# AICat.net
KiCad netlist of a schematic drawn in Altium Designer
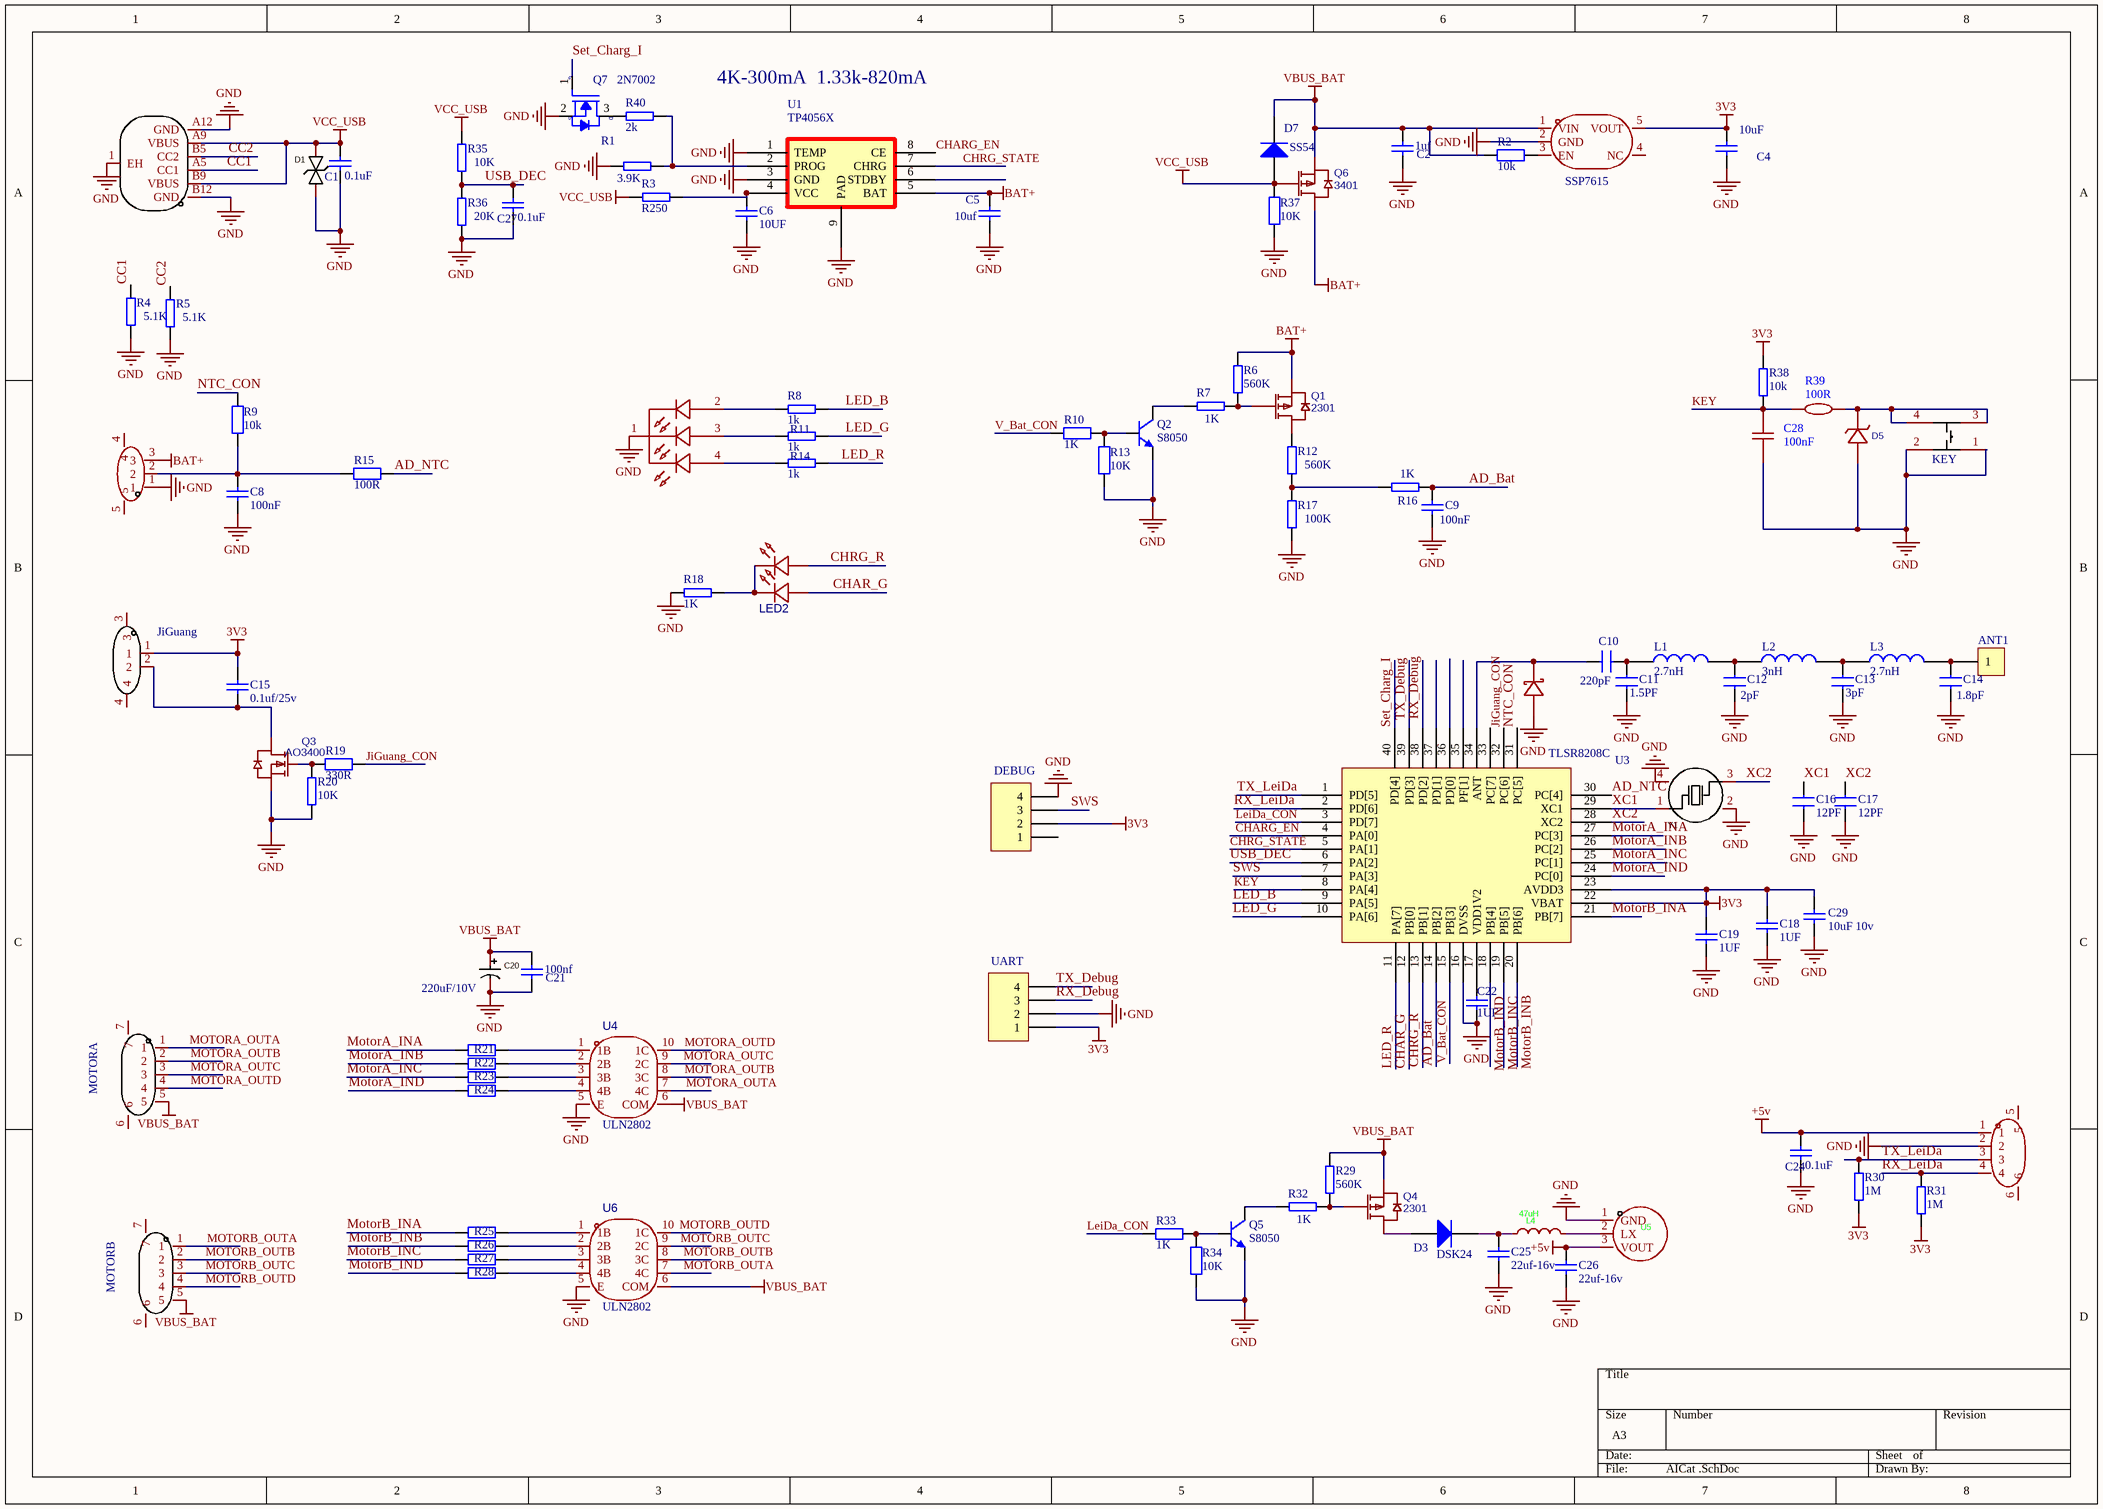
[diagram p0: AICat .SchDoc]

(export (version "E")
  (design (tool "Eeschema 10.0.6"))
  (components
    (comp (ref "ANT1")
      (value "~")
      (footprint "tp")
      (description "Connector")
      (libsource (lib "*") (part "CON1"))
    )
    (comp (ref "BAT1")
      (value "BX-PH2.0-3PWT")
      (footprint "HDR-TH_3P-P2.50_ZX-XH2.54-3PWZ")
      (libsource (lib "altium-import") (part "root_2_BX-PH2.0-3PWT_"))
    )
    (comp (ref "C1")
      (value "0.1uF")
      (footprint "0603_C")
      (description "Capacitor")
      (fields (field (name "PUBLISHER") "Altium Limited"))
      (libsource (lib "*") (part "Cap"))
    )
    (comp (ref "C2")
      (value "1uf")
      (footprint "0603_C")
      (description "无极电容")
      (libsource (lib "电容电阻电感保险") (part "Cap1"))
    )
    (comp (ref "C4")
      (value "10uF")
      (footprint "0603_C")
      (description "Capacitor")
      (fields (field (name "PUBLISHER") "Altium Limited"))
      (libsource (lib "*") (part "Cap"))
    )
    (comp (ref "C5")
      (value "10uf")
      (footprint "0603_C")
      (description "Capacitor")
      (fields (field (name "PUBLISHER") "Altium Limited"))
      (libsource (lib "*") (part "Cap"))
    )
    (comp (ref "C6") (value "10UF") (footprint "0603_c") (libsource (lib "DIY") (part "CAP")))
    (comp (ref "C8") (value "100nF") (footprint "0603_C") (libsource (lib "DIY") (part "CAP")))
    (comp (ref "C9") (value "100nF") (footprint "0603_C") (libsource (lib "DIY") (part "CAP")))
    (comp (ref "C10")
      (value "220pF")
      (footprint "C0402")
      (description "Capacitor")
      (libsource (lib "*") (part "CAP"))
    )
    (comp (ref "C11")
      (value "1.5PF")
      (footprint "C0402")
      (description "Capacitor")
      (libsource (lib "*") (part "CAP"))
    )
    (comp (ref "C12")
      (value "2pF")
      (footprint "C0402")
      (description "Capacitor")
      (libsource (lib "*") (part "CAP"))
    )
    (comp (ref "C13")
      (value "3pF")
      (footprint "C0402")
      (description "Capacitor")
      (libsource (lib "*") (part "CAP"))
    )
    (comp (ref "C14")
      (value "1.8pF")
      (footprint "C0402")
      (description "Capacitor")
      (libsource (lib "*") (part "CAP"))
    )
    (comp (ref "C15")
      (value "0.1uf/25v")
      (footprint "0603_C")
      (description "Capacitor")
      (fields (field (name "PUBLISHER") "Altium Limited"))
      (libsource (lib "*") (part "Cap"))
    )
    (comp (ref "C16")
      (value "12PF")
      (footprint "0603_c")
      (description "Capacitor")
      (libsource (lib "*") (part "CAP"))
    )
    (comp (ref "C17")
      (value "12PF")
      (footprint "0603_c")
      (description "Capacitor")
      (libsource (lib "*") (part "CAP"))
    )
    (comp (ref "C18") (value "1UF") (footprint "0603_c") (libsource (lib "DIY") (part "CAP")))
    (comp (ref "C19") (value "1UF") (footprint "0603_c") (libsource (lib "DIY") (part "CAP")))
    (comp (ref "C20")
      (value "220uF/10V")
      (footprint "SMD 6.3*5.4 电解")
      (fields (field (name "MANUFACTURER PART") "RVT1A221M0605"))
      (libsource (lib "altium-import") (part "root_0_RVT1A221M0605_C72494_"))
    )
    (comp (ref "C21")
      (value "100nf")
      (footprint "0603_C")
      (description "无极电容")
      (libsource (lib "电容电阻电感保险") (part "Cap1"))
    )
    (comp (ref "C22") (value "1UF") (footprint "0603_c") (libsource (lib "DIY") (part "CAP")))
    (comp (ref "C24")
      (value "0.1uF")
      (footprint "0603_C")
      (description "Capacitor")
      (fields (field (name "PUBLISHER") "Altium Limited"))
      (libsource (lib "*") (part "Cap"))
    )
    (comp (ref "C25")
      (value "22uf-16v")
      (footprint "0805_c")
      (description "无极电容")
      (libsource (lib "电容电阻电感保险") (part "Cap1"))
    )
    (comp (ref "C26")
      (value "22uf-16v")
      (footprint "0805_c")
      (description "无极电容")
      (libsource (lib "电容电阻电感保险") (part "Cap1"))
    )
    (comp (ref "C27")
      (value "0.1uF")
      (footprint "0603_C")
      (description "Capacitor")
      (fields (field (name "PUBLISHER") "Altium Limited"))
      (libsource (lib "*") (part "Cap"))
    )
    (comp (ref "C28")
      (value "100nF")
      (footprint "0603_c")
      (libsource (lib "altium-import") (part "root_1_CAP_0603_"))
    )
    (comp (ref "C29")
      (value "10uF 10v")
      (footprint "0603_C")
      (description "Capacitor")
      (fields (field (name "PUBLISHER") "Altium Limited"))
      (libsource (lib "*") (part "Cap"))
    )
    (comp (ref "CN1")
      (value "JiGuang")
      (footprint "CONN-SMD_2P-P1.25-LT")
      (fields (field (name "MANUFACTURER PART") "HC-1.25-2PLT"))
      (libsource (lib "altium-import") (part "root_0_mirrored_HC-1.25-2PLT_"))
    )
    (comp (ref "CN2")
      (value "HC-1.25-4PLT")
      (footprint "CONN-SMD_4P-P1.25_LT")
      (libsource (lib "altium-import") (part "root_0_HC-1.25-4PLT_"))
    )
    (comp (ref "D1")
      (value "SMF5.0CA_C726939")
      (footprint "SOD-123 双向")
      (fields (field (name "MANUFACTURER PART") "SMF5.0CA"))
      (libsource (lib "altium-import") (part "root_1_SMF5.0CA_C726939_"))
    )
    (comp (ref "D2")
      (value "SE6V3LHN102T 6.3v单向")
      (footprint "0402-D")
      (libsource (lib "altium-import") (part "root_3_TPNSR05F20NXT5G_"))
    )
    (comp (ref "D3")
      (value "DSK24")
      (footprint "SOD-123FL")
      (description "High Conductance Fast Diode")
      (fields (field (name "PUBLISHER") "Altium Limited"))
      (libsource (lib "Miscellaneous Devices") (part "Diode 1N4148"))
    )
    (comp (ref "D5")
      (value "esd5z5.0t1g-ms")
      (footprint "SOD-523_L1.2-W0.8-LS1.6-RD")
      (fields (field (name "MANUFACTURERPART") "ESD5Z5.0T1G-MS"))
      (libsource (lib "altium-import") (part "root_3_esd5z5.0t1g-ms_"))
    )
    (comp (ref "D7")
      (value "SS54")
      (footprint "SMA")
      (description "High Conductance Fast Diode")
      (fields (field (name "PUBLISHER") "Altium Limited"))
      (libsource (lib "Miscellaneous Devices") (part "Diode 1N4148"))
    )
    (comp (ref "J1")
      (value "MOTORA")
      (footprint "CONN-SMD_1.25-5PLT")
      (fields (field (name "MANUFACTURER PART") "HC-1.25-5PLT"))
      (libsource (lib "altium-import") (part "root_0_mirrored_HC-1.25-5PLT_"))
    )
    (comp (ref "J2")
      (value "MOTORB")
      (footprint "CONN-SMD_1.25-5PLT")
      (fields (field (name "MANUFACTURER PART") "HC-1.25-5PLT"))
      (libsource (lib "altium-import") (part "root_0_mirrored_HC-1.25-5PLT_"))
    )
    (comp (ref "K1")
      (value "KEY")
      (footprint "KEY_SMD_4P")
      (fields (field (name "MANUFACTURER PART") "TS-1002S-05026C"))
      (libsource (lib "altium-import") (part "root_2_TS-1002S-05026C_"))
    )
    (comp (ref "L1") (value "2.7nH") (footprint "R0402") (libsource (lib "*") (part "INDUCTOR")))
    (comp (ref "L2") (value "3nH") (footprint "R0402") (libsource (lib "*") (part "INDUCTOR")))
    (comp (ref "L3") (value "2.7nH") (footprint "R0402") (libsource (lib "*") (part "INDUCTOR")))
    (comp (ref "L4")
      (value "47uH")
      (footprint "IND-SMD_L3.5-W3.0_CD31")
      (fields (field (name "MANUFACTURER PART") "CD31-470M 47UH"))
      (libsource (lib "altium-import") (part "root_0_CD31-470M 47UH_"))
    )
    (comp (ref "LED1")
      (value "XL-A3528RGBC-BM")
      (footprint "LED-ARRAY-SMD_4P-L3.2-W2.8-LS3.5-BL_XL-A3528RGBC-BM")
      (libsource (lib "altium-import") (part "root_2_XL-A3528RGBC-BM_"))
    )
    (comp (ref "LED2")
      (value "*")
      (footprint "LED-SMD_4P-L3.2-W1.6-TL_XL-3216SURUGC")
      (libsource (lib "altium-import") (part "root_0_TJ-S2012SW8TCGLC2R2G-A5_"))
    )
    (comp (ref "P1")
      (value "DEBUG")
      (footprint "SIP4-2.54")
      (description "Header, 4-Pin")
      (fields (field (name "PUBLISHER") "Altium Limited"))
      (libsource (lib "Miscellaneous Connectors") (part "Header 4"))
    )
    (comp (ref "P2")
      (value "UART")
      (footprint "SIP4-2.54")
      (description "Header, 4-Pin")
      (fields (field (name "PUBLISHER") "Altium Limited"))
      (libsource (lib "Miscellaneous Connectors") (part "Header 4"))
    )
    (comp (ref "Q1")
      (value "2301")
      (footprint "SOT-23")
      (fields (field (name "BOM_MANUFACTURER PART") "CJ3401") (field (name "BOM_SUPPLIER PART") "C13799"))
      (libsource (lib "altium-import") (part "root_2_mirrored_CJ3401_"))
    )
    (comp (ref "Q2")
      (value "S8050")
      (footprint "SOT-23(SOT-23-3)")
      (description "NPN三极管")
      (libsource (lib "二三极管mos可控硅") (part "NPN_sot23"))
    )
    (comp (ref "Q3")
      (value "AO3400")
      (footprint "SOT-23")
      (fields
        (field (name "BOM_SUPPLIER PART") "C2890442")
        (field (name "BOM_MANUFACTURER PART") "JMTL3400A")
        (field (name "CONTRIBUTOR") "LCSC")
      )
      (libsource (lib "altium-import") (part "root_0_mirrored_JMTL3400A_"))
    )
    (comp (ref "Q4")
      (value "2301")
      (footprint "SOT-23")
      (fields (field (name "BOM_MANUFACTURER PART") "CJ3401") (field (name "BOM_SUPPLIER PART") "C13799"))
      (libsource (lib "altium-import") (part "root_2_mirrored_CJ3401_"))
    )
    (comp (ref "Q5")
      (value "S8050")
      (footprint "SOT-23(SOT-23-3)")
      (description "NPN三极管")
      (libsource (lib "二三极管mos可控硅") (part "NPN_sot23"))
    )
    (comp (ref "Q6")
      (value "3401")
      (footprint "SOT-23")
      (fields (field (name "BOM_MANUFACTURER PART") "CJ3401") (field (name "BOM_SUPPLIER PART") "C13799"))
      (libsource (lib "altium-import") (part "root_2_mirrored_CJ3401_"))
    )
    (comp (ref "Q7") (value "2N7002") (footprint "SOT-23") (libsource (lib "*") (part "AO3400_SOT23")))
    (comp (ref "R1") (value "3.9K") (footprint "0603_R") (libsource (lib "DIY") (part "RES")))
    (comp (ref "R2")
      (value "10k")
      (footprint "0603_R")
      (description "Resistor")
      (fields (field (name "PUBLISHER") "Altium Limited"))
      (libsource (lib "") (part "Res2_2"))
    )
    (comp (ref "R3") (value "R250") (footprint "1206_R") (libsource (lib "DIY") (part "RES")))
    (comp (ref "R4") (value "5.1K") (footprint "0603_R") (libsource (lib "DIY") (part "RES")))
    (comp (ref "R5") (value "5.1K") (footprint "0603_R") (libsource (lib "DIY") (part "RES")))
    (comp (ref "R6") (value "560K") (footprint "0603_R") (libsource (lib "*") (part "RES")))
    (comp (ref "R7") (value "1K") (footprint "0603_R") (libsource (lib "") (part "RES_1")))
    (comp (ref "R8") (value "1k") (footprint "0603_R") (libsource (lib "DIY") (part "RES")))
    (comp (ref "R9")
      (value "10k")
      (footprint "0603_R")
      (description "Resistor")
      (fields (field (name "PUBLISHER") "Altium Limited"))
      (libsource (lib "*") (part "Res2"))
    )
    (comp (ref "R10")
      (value "1K")
      (footprint "0603_r")
      (description "Resistor")
      (fields (field (name "PUBLISHER") "Altium Limited"))
      (libsource (lib "") (part "Res2_3"))
    )
    (comp (ref "R11") (value "1k") (footprint "0603_R") (libsource (lib "DIY") (part "RES")))
    (comp (ref "R12") (value "560K") (footprint "0603_R") (libsource (lib "DIY") (part "RES")))
    (comp (ref "R13")
      (value "10K")
      (footprint "0603_r")
      (description "Resistor")
      (fields (field (name "PUBLISHER") "Altium Limited"))
      (libsource (lib "") (part "Res2_2"))
    )
    (comp (ref "R14") (value "1k") (footprint "0603_R") (libsource (lib "DIY") (part "RES")))
    (comp (ref "R15")
      (value "100R")
      (footprint "0603_R")
      (description "Resistor")
      (fields (field (name "PUBLISHER") "Altium Limited"))
      (libsource (lib "") (part "Res2_4"))
    )
    (comp (ref "R16") (value "1K") (footprint "0603_R") (libsource (lib "DIY") (part "RES")))
    (comp (ref "R17") (value "100K") (footprint "0603_R") (libsource (lib "DIY") (part "RES")))
    (comp (ref "R18") (value "1K") (footprint "0603_R") (libsource (lib "DIY") (part "RES")))
    (comp (ref "R19")
      (value "330R")
      (footprint "0603_R")
      (description "Resistor")
      (fields (field (name "PUBLISHER") "Altium Limited"))
      (libsource (lib "*") (part "Res2"))
    )
    (comp (ref "R20") (value "10K") (footprint "0603_R") (libsource (lib "DIY") (part "RES")))
    (comp (ref "R21")
      (value "330R")
      (footprint "0603_R")
      (description "Resistor")
      (fields (field (name "PUBLISHER") "Altium Limited"))
      (libsource (lib "") (part "Res2_1"))
    )
    (comp (ref "R22")
      (value "330R")
      (footprint "0603_R")
      (description "Resistor")
      (fields (field (name "PUBLISHER") "Altium Limited"))
      (libsource (lib "") (part "Res2_1"))
    )
    (comp (ref "R23")
      (value "330R")
      (footprint "0603_R")
      (description "Resistor")
      (fields (field (name "PUBLISHER") "Altium Limited"))
      (libsource (lib "") (part "Res2_1"))
    )
    (comp (ref "R24")
      (value "330R")
      (footprint "0603_R")
      (description "Resistor")
      (fields (field (name "PUBLISHER") "Altium Limited"))
      (libsource (lib "") (part "Res2_1"))
    )
    (comp (ref "R25")
      (value "330R")
      (footprint "0603_R")
      (description "Resistor")
      (fields (field (name "PUBLISHER") "Altium Limited"))
      (libsource (lib "") (part "Res2_1"))
    )
    (comp (ref "R26")
      (value "330R")
      (footprint "0603_R")
      (description "Resistor")
      (fields (field (name "PUBLISHER") "Altium Limited"))
      (libsource (lib "") (part "Res2_1"))
    )
    (comp (ref "R27")
      (value "330R")
      (footprint "0603_R")
      (description "Resistor")
      (fields (field (name "PUBLISHER") "Altium Limited"))
      (libsource (lib "") (part "Res2_1"))
    )
    (comp (ref "R28")
      (value "330R")
      (footprint "0603_R")
      (description "Resistor")
      (fields (field (name "PUBLISHER") "Altium Limited"))
      (libsource (lib "") (part "Res2_1"))
    )
    (comp (ref "R29") (value "560K") (footprint "0603_R") (libsource (lib "*") (part "RES")))
    (comp (ref "R30") (value "1M") (footprint "0603_R") (libsource (lib "*") (part "RES")))
    (comp (ref "R31") (value "1M") (footprint "0603_R") (libsource (lib "*") (part "RES")))
    (comp (ref "R32") (value "1K") (footprint "0603_R") (libsource (lib "") (part "RES_1")))
    (comp (ref "R33")
      (value "1K")
      (footprint "0603_r")
      (description "Resistor")
      (fields (field (name "PUBLISHER") "Altium Limited"))
      (libsource (lib "") (part "Res2_3"))
    )
    (comp (ref "R34")
      (value "10K")
      (footprint "0603_r")
      (description "Resistor")
      (fields (field (name "PUBLISHER") "Altium Limited"))
      (libsource (lib "") (part "Res2_2"))
    )
    (comp (ref "R35") (value "10K") (footprint "0603_R") (libsource (lib "DIY") (part "RES")))
    (comp (ref "R36") (value "20K") (footprint "0603_R") (libsource (lib "DIY") (part "RES")))
    (comp (ref "R37")
      (value "10K")
      (footprint "0603_R")
      (description "Resistor")
      (fields (field (name "PUBLISHER") "Altium Limited"))
      (libsource (lib "*") (part "Res2"))
    )
    (comp (ref "R38") (value "10k") (footprint "0603_R") (libsource (lib "DIY") (part "RES")))
    (comp (ref "R39")
      (value "100R")
      (footprint "0603_r")
      (libsource (lib "altium-import") (part "root_2_Res_0603_"))
    )
    (comp (ref "R40") (value "2k") (footprint "0603_R") (libsource (lib "DIY") (part "RES")))
    (comp (ref "U1")
      (value "TP4056X")
      (footprint "SOP8-9")
      (description "TP4056")
      (libsource (lib "芯片") (part "TP4056"))
    )
    (comp (ref "U2")
      (value "SSP7615")
      (footprint "SOT-23-5")
      (libsource (lib "altium-import") (part "root_0_SSP7615-33M5R_"))
    )
    (comp (ref "U3")
      (value "TLSR8208C")
      (footprint "QFN-40_L5.0-W5.0-P0.40-BL-EP3.7")
      (libsource (lib "MyLib") (part "TLSR8208C"))
    )
    (comp (ref "U4")
      (value "ULN2802")
      (footprint "ESSOP-10")
      (libsource (lib "altium-import") (part "root_0_ULN2802_C2828555_"))
    )
    (comp (ref "U5")
      (value "HE9116A50NR")
      (footprint "SOT-23")
      (libsource (lib "altium-import") (part "root_0_HE9116A50NR_"))
    )
    (comp (ref "U6")
      (value "ULN2802")
      (footprint "ESSOP-10")
      (libsource (lib "altium-import") (part "root_0_ULN2802_C2828555_"))
    )
    (comp (ref "USB1")
      (value "TYPE-C 6P")
      (footprint "TPYE-C-6")
      (fields (field (name "MANUFACTURER PART") "TYPE-C 6P LTH6.5"))
      (libsource (lib "altium-import") (part "root_2_TYPE-C 6P LTH6.5_"))
    )
    (comp (ref "Y1")
      (value "24MHz +-20PPM")
      (footprint "CRYSTAL-SMD_4P-L3.2-W2.5")
      (fields (field (name "MANUFACTURER PART") "TAXM13.56M4RLBCCT2T"))
      (libsource (lib "altium-import") (part "root_0_TAXM13.56M4RLBCCT2T_"))
    )
  )
  (nets
    (net (code "1") (name "+5v") (class "Default")
      (node (ref "C24") (pin "2") (pinfunction "2_2") (pintype "passive"))
      (node (ref "C26") (pin "1") (pinfunction "1_1") (pintype "passive"))
      (node (ref "CN2") (pin "1") (pinfunction "1_1") (pintype "passive"))
      (node (ref "U5") (pin "3") (pinfunction "VOUT_3") (pintype "passive"))
    )
    (net (code "2") (name "/AD_Bat") (class "Default")
      (node (ref "C9") (pin "2") (pintype "passive"))
      (node (ref "R16") (pin "1") (pinfunction "1_1") (pintype "passive"))
      (node (ref "U3") (pin "14") (pinfunction "PB[2]_14") (pintype "passive"))
    )
    (net (code "3") (name "/AD_NTC") (class "Default")
      (node (ref "R15") (pin "1") (pinfunction "1_1") (pintype "passive"))
      (node (ref "U3") (pin "30") (pinfunction "PC[4]_30") (pintype "passive"))
    )
    (net (code "4") (name "/CC1") (class "Default")
      (node (ref "R4") (pin "1") (pinfunction "1_1") (pintype "passive"))
      (node (ref "USB1") (pin "A5") (pinfunction "CC1_A5") (pintype "passive"))
    )
    (net (code "5") (name "/CC2") (class "Default")
      (node (ref "R5") (pin "1") (pinfunction "1_1") (pintype "passive"))
      (node (ref "USB1") (pin "B5") (pinfunction "CC2_B5") (pintype "passive"))
    )
    (net (code "6") (name "/CHARG_EN") (class "Default")
      (node (ref "U1") (pin "8") (pinfunction "CE_8") (pintype "passive"))
      (node (ref "U3") (pin "4") (pinfunction "PA[0]_4") (pintype "passive"))
    )
    (net (code "7") (name "/CHAR_G") (class "Default")
      (node (ref "LED2") (pin "3") (pinfunction "A_3") (pintype "passive"))
      (node (ref "U3") (pin "12") (pinfunction "PB[0]_12") (pintype "passive"))
    )
    (net (code "8") (name "/CHRG_R") (class "Default")
      (node (ref "LED2") (pin "1") (pinfunction "A_1") (pintype "passive"))
      (node (ref "U3") (pin "13") (pinfunction "PB[1]_13") (pintype "passive"))
    )
    (net (code "9") (name "/CHRG_STATE") (class "Default")
      (node (ref "U1") (pin "7") (pinfunction "CHRG_7") (pintype "passive"))
      (node (ref "U3") (pin "5") (pinfunction "PA[1]_5") (pintype "passive"))
    )
    (net (code "10") (name "/JiGuang_CON") (class "Default")
      (node (ref "R19") (pin "2") (pinfunction "2_2") (pintype "passive"))
      (node (ref "U3") (pin "32") (pinfunction "PC[6]_32") (pintype "passive"))
    )
    (net (code "11") (name "/KEY") (class "Default")
      (node (ref "C28") (pin "2") (pinfunction "2_2") (pintype "passive"))
      (node (ref "R38") (pin "1") (pinfunction "1_1") (pintype "passive"))
      (node (ref "R39") (pin "2") (pinfunction "2_2") (pintype "passive"))
      (node (ref "U3") (pin "8") (pinfunction "PA[4]_8") (pintype "passive"))
    )
    (net (code "12") (name "/LED_B") (class "Default")
      (node (ref "R8") (pin "2") (pinfunction "2_2") (pintype "passive"))
      (node (ref "U3") (pin "9") (pinfunction "PA[5]_9") (pintype "passive"))
    )
    (net (code "13") (name "/LED_G") (class "Default")
      (node (ref "R11") (pin "2") (pinfunction "2_2") (pintype "passive"))
      (node (ref "U3") (pin "10") (pinfunction "PA[6]_10") (pintype "passive"))
    )
    (net (code "14") (name "/LED_R") (class "Default")
      (node (ref "R14") (pin "2") (pinfunction "2_2") (pintype "passive"))
      (node (ref "U3") (pin "11") (pinfunction "PA[7]_11") (pintype "passive"))
    )
    (net (code "15") (name "/LeiDa_CON") (class "Default")
      (node (ref "R33") (pin "2") (pinfunction "2_2") (pintype "passive"))
      (node (ref "U3") (pin "3") (pinfunction "PD[7]_3") (pintype "passive"))
    )
    (net (code "16") (name "/MOTORA_OUTA") (class "Default")
      (node (ref "J1") (pin "1") (pinfunction "1_1") (pintype "passive"))
      (node (ref "U4") (pin "7") (pinfunction "4C_7") (pintype "passive"))
    )
    (net (code "17") (name "/MOTORA_OUTB") (class "Default")
      (node (ref "J1") (pin "2") (pinfunction "2_2") (pintype "passive"))
      (node (ref "U4") (pin "8") (pinfunction "3C_8") (pintype "passive"))
    )
    (net (code "18") (name "/MOTORA_OUTC") (class "Default")
      (node (ref "J1") (pin "3") (pinfunction "3_3") (pintype "passive"))
      (node (ref "U4") (pin "9") (pinfunction "2C_9") (pintype "passive"))
    )
    (net (code "19") (name "/MOTORA_OUTD") (class "Default")
      (node (ref "J1") (pin "4") (pinfunction "4_4") (pintype "passive"))
      (node (ref "U4") (pin "10") (pinfunction "1C_10") (pintype "passive"))
    )
    (net (code "20") (name "/MOTORB_OUTA") (class "Default")
      (node (ref "J2") (pin "1") (pinfunction "1_1") (pintype "passive"))
      (node (ref "U6") (pin "7") (pinfunction "4C_7") (pintype "passive"))
    )
    (net (code "21") (name "/MOTORB_OUTB") (class "Default")
      (node (ref "J2") (pin "2") (pinfunction "2_2") (pintype "passive"))
      (node (ref "U6") (pin "8") (pinfunction "3C_8") (pintype "passive"))
    )
    (net (code "22") (name "/MOTORB_OUTC") (class "Default")
      (node (ref "J2") (pin "3") (pinfunction "3_3") (pintype "passive"))
      (node (ref "U6") (pin "9") (pinfunction "2C_9") (pintype "passive"))
    )
    (net (code "23") (name "/MOTORB_OUTD") (class "Default")
      (node (ref "J2") (pin "4") (pinfunction "4_4") (pintype "passive"))
      (node (ref "U6") (pin "10") (pinfunction "1C_10") (pintype "passive"))
    )
    (net (code "24") (name "/MotorA_INA") (class "Default")
      (node (ref "R21") (pin "2") (pinfunction "2_2") (pintype "passive"))
      (node (ref "U3") (pin "27") (pinfunction "PC[3]_27") (pintype "passive"))
    )
    (net (code "25") (name "/MotorA_INB") (class "Default")
      (node (ref "R22") (pin "2") (pinfunction "2_2") (pintype "passive"))
      (node (ref "U3") (pin "26") (pinfunction "PC[2]_26") (pintype "passive"))
    )
    (net (code "26") (name "/MotorA_INC") (class "Default")
      (node (ref "R23") (pin "2") (pinfunction "2_2") (pintype "passive"))
      (node (ref "U3") (pin "25") (pinfunction "PC[1]_25") (pintype "passive"))
    )
    (net (code "27") (name "/MotorA_IND") (class "Default")
      (node (ref "R24") (pin "2") (pinfunction "2_2") (pintype "passive"))
      (node (ref "U3") (pin "24") (pinfunction "PC[0]_24") (pintype "passive"))
    )
    (net (code "28") (name "/MotorB_INA") (class "Default")
      (node (ref "R25") (pin "2") (pinfunction "2_2") (pintype "passive"))
      (node (ref "U3") (pin "21") (pinfunction "PB[7]_21") (pintype "passive"))
    )
    (net (code "29") (name "/MotorB_INB") (class "Default")
      (node (ref "R26") (pin "2") (pinfunction "2_2") (pintype "passive"))
      (node (ref "U3") (pin "20") (pinfunction "PB[6]_20") (pintype "passive"))
    )
    (net (code "30") (name "/MotorB_INC") (class "Default")
      (node (ref "R27") (pin "2") (pinfunction "2_2") (pintype "passive"))
      (node (ref "U3") (pin "19") (pinfunction "PB[5]_19") (pintype "passive"))
    )
    (net (code "31") (name "/MotorB_IND") (class "Default")
      (node (ref "R28") (pin "2") (pinfunction "2_2") (pintype "passive"))
      (node (ref "U3") (pin "18") (pinfunction "PB[4]_18") (pintype "passive"))
    )
    (net (code "32") (name "/NTC_CON") (class "Default")
      (node (ref "R9") (pin "2") (pinfunction "2_2") (pintype "passive"))
      (node (ref "U3") (pin "31") (pinfunction "PC[5]_31") (pintype "passive"))
    )
    (net (code "33") (name "/RX_Debug") (class "Default")
      (node (ref "P2") (pin "3") (pinfunction "3_3") (pintype "passive"))
      (node (ref "U3") (pin "38") (pinfunction "PD[2]_38") (pintype "passive"))
    )
    (net (code "34") (name "/RX_LeiDa") (class "Default")
      (node (ref "CN2") (pin "4") (pinfunction "4_4") (pintype "passive"))
      (node (ref "R31") (pin "1") (pintype "passive"))
      (node (ref "U3") (pin "2") (pinfunction "PD[6]_2") (pintype "passive"))
    )
    (net (code "35") (name "/SWS") (class "Default")
      (node (ref "P1") (pin "3") (pinfunction "3_3") (pintype "passive"))
      (node (ref "U3") (pin "7") (pinfunction "PA[3]_7") (pintype "passive"))
    )
    (net (code "36") (name "/Set_Charg_I") (class "Default")
      (node (ref "Q7") (pin "1") (pinfunction "GATE_1") (pintype "passive"))
      (node (ref "U3") (pin "40") (pinfunction "PD[4]_40") (pintype "passive"))
    )
    (net (code "37") (name "/TX_Debug") (class "Default")
      (node (ref "P2") (pin "4") (pinfunction "4_4") (pintype "passive"))
      (node (ref "U3") (pin "39") (pinfunction "PD[3]_39") (pintype "passive"))
    )
    (net (code "38") (name "/TX_LeiDa") (class "Default")
      (node (ref "CN2") (pin "3") (pinfunction "3_3") (pintype "passive"))
      (node (ref "R30") (pin "1") (pintype "passive"))
      (node (ref "U3") (pin "1") (pinfunction "PD[5]_1") (pintype "passive"))
    )
    (net (code "39") (name "/USB_DEC") (class "Default")
      (node (ref "C27") (pin "2") (pinfunction "2_2") (pintype "passive"))
      (node (ref "R35") (pin "2") (pinfunction "2_2") (pintype "passive"))
      (node (ref "R36") (pin "1") (pinfunction "1_1") (pintype "passive"))
      (node (ref "U3") (pin "6") (pinfunction "PA[2]_6") (pintype "passive"))
    )
    (net (code "40") (name "/V_Bat_CON") (class "Default")
      (node (ref "R10") (pin "2") (pinfunction "2_2") (pintype "passive"))
      (node (ref "U3") (pin "15") (pinfunction "PB[3]_15") (pintype "passive"))
    )
    (net (code "41") (name "/XC1") (class "Default")
      (node (ref "C16") (pin "2") (pinfunction "2_2") (pintype "passive"))
      (node (ref "U3") (pin "29") (pinfunction "XC1_29") (pintype "passive"))
      (node (ref "Y1") (pin "1") (pinfunction "OSC1_1") (pintype "passive"))
    )
    (net (code "42") (name "/XC2") (class "Default")
      (node (ref "C17") (pin "2") (pinfunction "2_2") (pintype "passive"))
      (node (ref "U3") (pin "28") (pinfunction "XC2_28") (pintype "passive"))
      (node (ref "Y1") (pin "3") (pinfunction "OSC2_3") (pintype "passive"))
    )
    (net (code "43") (name "3V3") (class "Default")
      (node (ref "C15") (pin "2") (pinfunction "2_2") (pintype "passive"))
      (node (ref "C18") (pin "1") (pintype "passive"))
      (node (ref "C19") (pin "1") (pintype "passive"))
      (node (ref "C29") (pin "2") (pinfunction "2_2") (pintype "passive"))
      (node (ref "C4") (pin "2") (pinfunction "2_2") (pintype "passive"))
      (node (ref "CN1") (pin "1") (pinfunction "1_1") (pintype "passive"))
      (node (ref "P1") (pin "2") (pinfunction "2_2") (pintype "passive"))
      (node (ref "P2") (pin "1") (pinfunction "1_1") (pintype "passive"))
      (node (ref "R30") (pin "2") (pintype "passive"))
      (node (ref "R31") (pin "2") (pintype "passive"))
      (node (ref "R38") (pin "2") (pinfunction "2_2") (pintype "passive"))
      (node (ref "U2") (pin "5") (pinfunction "VOUT_5") (pintype "passive"))
      (node (ref "U3") (pin "22") (pinfunction "VBAT_22") (pintype "passive"))
      (node (ref "U3") (pin "23") (pinfunction "AVDD3_23") (pintype "passive"))
    )
    (net (code "44") (name "BAT+") (class "Default")
      (node (ref "BAT1") (pin "3") (pinfunction "3_3") (pintype "passive"))
      (node (ref "C5") (pin "1") (pinfunction "1_1") (pintype "passive"))
      (node (ref "Q1") (pin "2") (pinfunction "S_2") (pintype "passive"))
      (node (ref "Q6") (pin "3") (pinfunction "D_3") (pintype "passive"))
      (node (ref "R6") (pin "1") (pintype "passive"))
      (node (ref "U1") (pin "5") (pinfunction "BAT_5") (pintype "passive"))
    )
    (net (code "45") (name "GND") (class "Default")
      (node (ref "BAT1") (pin "1") (pinfunction "1_1") (pintype "passive"))
      (node (ref "C1") (pin "1") (pinfunction "1_1") (pintype "passive"))
      (node (ref "C11") (pin "1") (pinfunction "1_1") (pintype "passive"))
      (node (ref "C12") (pin "1") (pinfunction "1_1") (pintype "passive"))
      (node (ref "C13") (pin "1") (pinfunction "1_1") (pintype "passive"))
      (node (ref "C14") (pin "1") (pinfunction "1_1") (pintype "passive"))
      (node (ref "C16") (pin "1") (pinfunction "1_1") (pintype "passive"))
      (node (ref "C17") (pin "1") (pinfunction "1_1") (pintype "passive"))
      (node (ref "C18") (pin "2") (pintype "passive"))
      (node (ref "C19") (pin "2") (pintype "passive"))
      (node (ref "C2") (pin "1") (pinfunction "1_1") (pintype "passive"))
      (node (ref "C20") (pin "2") (pinfunction "2_2") (pintype "passive"))
      (node (ref "C21") (pin "1") (pinfunction "1_1") (pintype "passive"))
      (node (ref "C22") (pin "1") (pintype "passive"))
      (node (ref "C24") (pin "1") (pinfunction "1_1") (pintype "passive"))
      (node (ref "C25") (pin "2") (pinfunction "2_2") (pintype "passive"))
      (node (ref "C26") (pin "2") (pinfunction "2_2") (pintype "passive"))
      (node (ref "C27") (pin "1") (pinfunction "1_1") (pintype "passive"))
      (node (ref "C28") (pin "1") (pinfunction "1_1") (pintype "passive"))
      (node (ref "C29") (pin "1") (pinfunction "1_1") (pintype "passive"))
      (node (ref "C4") (pin "1") (pinfunction "1_1") (pintype "passive"))
      (node (ref "C5") (pin "2") (pinfunction "2_2") (pintype "passive"))
      (node (ref "C6") (pin "1") (pintype "passive"))
      (node (ref "C8") (pin "2") (pintype "passive"))
      (node (ref "C9") (pin "1") (pintype "passive"))
      (node (ref "CN2") (pin "2") (pinfunction "2_2") (pintype "passive"))
      (node (ref "D1") (pin "1") (pinfunction "1_1") (pintype "passive"))
      (node (ref "D2") (pin "2") (pinfunction "A_2") (pintype "passive"))
      (node (ref "D5") (pin "2") (pinfunction "A_2") (pintype "passive"))
      (node (ref "K1") (pin "1") (pinfunction "1_1") (pintype "passive"))
      (node (ref "K1") (pin "2") (pinfunction "2_2") (pintype "passive"))
      (node (ref "LED1") (pin "1") (pinfunction "1_1") (pintype "passive"))
      (node (ref "P1") (pin "4") (pinfunction "4_4") (pintype "passive"))
      (node (ref "P2") (pin "2") (pinfunction "2_2") (pintype "passive"))
      (node (ref "Q2") (pin "2") (pinfunction "E_2") (pintype "passive"))
      (node (ref "Q3") (pin "2") (pinfunction "S_2") (pintype "passive"))
      (node (ref "Q5") (pin "2") (pinfunction "E_2") (pintype "passive"))
      (node (ref "Q7") (pin "2") (pinfunction "SOURCE_2") (pintype "passive"))
      (node (ref "R1") (pin "1") (pinfunction "1_1") (pintype "passive"))
      (node (ref "R13") (pin "1") (pinfunction "1_1") (pintype "passive"))
      (node (ref "R17") (pin "2") (pinfunction "2_2") (pintype "passive"))
      (node (ref "R18") (pin "1") (pinfunction "1_1") (pintype "passive"))
      (node (ref "R20") (pin "1") (pinfunction "1_1") (pintype "passive"))
      (node (ref "R34") (pin "1") (pinfunction "1_1") (pintype "passive"))
      (node (ref "R36") (pin "2") (pinfunction "2_2") (pintype "passive"))
      (node (ref "R37") (pin "1") (pinfunction "1_1") (pintype "passive"))
      (node (ref "R4") (pin "2") (pinfunction "2_2") (pintype "passive"))
      (node (ref "R5") (pin "2") (pinfunction "2_2") (pintype "passive"))
      (node (ref "U1") (pin "1") (pinfunction "TEMP_1") (pintype "passive"))
      (node (ref "U1") (pin "3") (pinfunction "GND_3") (pintype "passive"))
      (node (ref "U1") (pin "9") (pinfunction "PAD_9") (pintype "passive"))
      (node (ref "U2") (pin "2") (pinfunction "GND_2") (pintype "passive"))
      (node (ref "U3") (pin "16") (pinfunction "DVSS_16") (pintype "passive"))
      (node (ref "U4") (pin "5") (pinfunction "E_5") (pintype "passive"))
      (node (ref "U5") (pin "1") (pinfunction "GND_1") (pintype "passive"))
      (node (ref "U6") (pin "5") (pinfunction "E_5") (pintype "passive"))
      (node (ref "USB1") (pin "1") (pinfunction "EH_1") (pintype "passive"))
      (node (ref "USB1") (pin "A12") (pinfunction "GND_A12") (pintype "passive"))
      (node (ref "USB1") (pin "B12") (pinfunction "GND_B12") (pintype "passive"))
      (node (ref "Y1") (pin "2") (pinfunction "GND_2") (pintype "passive"))
      (node (ref "Y1") (pin "4") (pinfunction "GND_4") (pintype "passive"))
    )
    (net (code "46") (name "Net-(ANT1-Pad1)") (class "Default")
      (node (ref "ANT1") (pin "1") (pinfunction "1_1") (pintype "passive"))
      (node (ref "C14") (pin "2") (pinfunction "2_2") (pintype "passive"))
      (node (ref "L3") (pin "2") (pinfunction "2_2") (pintype "passive"))
    )
    (net (code "47") (name "Net-(BAT1-Pad2)") (class "Default")
      (node (ref "BAT1") (pin "2") (pinfunction "2_2") (pintype "passive"))
      (node (ref "C8") (pin "1") (pintype "passive"))
      (node (ref "R15") (pin "2") (pinfunction "2_2") (pintype "passive"))
      (node (ref "R9") (pin "1") (pinfunction "1_1") (pintype "passive"))
    )
    (net (code "48") (name "Net-(C10-Pad2)") (class "Default")
      (node (ref "C10") (pin "2") (pinfunction "2_2") (pintype "passive"))
      (node (ref "C11") (pin "2") (pinfunction "2_2") (pintype "passive"))
      (node (ref "L1") (pin "1") (pinfunction "1_1") (pintype "passive"))
    )
    (net (code "49") (name "Net-(C12-Pad2)") (class "Default")
      (node (ref "C12") (pin "2") (pinfunction "2_2") (pintype "passive"))
      (node (ref "L1") (pin "2") (pinfunction "2_2") (pintype "passive"))
      (node (ref "L2") (pin "1") (pinfunction "1_1") (pintype "passive"))
    )
    (net (code "50") (name "Net-(C13-Pad2)") (class "Default")
      (node (ref "C13") (pin "2") (pinfunction "2_2") (pintype "passive"))
      (node (ref "L2") (pin "2") (pinfunction "2_2") (pintype "passive"))
      (node (ref "L3") (pin "1") (pinfunction "1_1") (pintype "passive"))
    )
    (net (code "51") (name "Net-(D2-C)") (class "Default")
      (node (ref "C10") (pin "1") (pinfunction "1_1") (pintype "passive"))
      (node (ref "D2") (pin "1") (pinfunction "C_1") (pintype "passive"))
      (node (ref "U3") (pin "34") (pinfunction "ANT_34") (pintype "passive"))
    )
    (net (code "52") (name "Net-(D3-A)") (class "Default")
      (node (ref "D3") (pin "1") (pinfunction "A_1") (pintype "passive"))
      (node (ref "Q4") (pin "3") (pinfunction "D_3") (pintype "passive"))
    )
    (net (code "53") (name "Net-(D3-K)") (class "Default")
      (node (ref "C25") (pin "1") (pinfunction "1_1") (pintype "passive"))
      (node (ref "D3") (pin "2") (pinfunction "K_2") (pintype "passive"))
      (node (ref "L4") (pin "1") (pinfunction "1_1") (pintype "passive"))
    )
    (net (code "54") (name "Net-(D5-C)") (class "Default")
      (node (ref "D5") (pin "1") (pinfunction "C_1") (pintype "passive"))
      (node (ref "K1") (pin "3") (pinfunction "3_3") (pintype "passive"))
      (node (ref "K1") (pin "4") (pinfunction "4_4") (pintype "passive"))
      (node (ref "R39") (pin "1") (pinfunction "1_1") (pintype "passive"))
    )
    (net (code "55") (name "Net-(LED1-Pad2)") (class "Default")
      (node (ref "LED1") (pin "2") (pinfunction "2_2") (pintype "passive"))
      (node (ref "R8") (pin "1") (pinfunction "1_1") (pintype "passive"))
    )
    (net (code "56") (name "Net-(LED1-Pad3)") (class "Default")
      (node (ref "LED1") (pin "3") (pinfunction "3_3") (pintype "passive"))
      (node (ref "R11") (pin "1") (pinfunction "1_1") (pintype "passive"))
    )
    (net (code "57") (name "Net-(LED1-Pad4)") (class "Default")
      (node (ref "LED1") (pin "4") (pinfunction "4_4") (pintype "passive"))
      (node (ref "R14") (pin "1") (pinfunction "1_1") (pintype "passive"))
    )
    (net (code "58") (name "Net-(LED2-K-Pad2)") (class "Default")
      (node (ref "LED2") (pin "2") (pinfunction "K_2") (pintype "passive"))
      (node (ref "LED2") (pin "4") (pinfunction "K_4") (pintype "passive"))
      (node (ref "R18") (pin "2") (pinfunction "2_2") (pintype "passive"))
    )
    (net (code "59") (name "Net-(Q1-D)") (class "Default")
      (node (ref "Q1") (pin "3") (pinfunction "D_3") (pintype "passive"))
      (node (ref "R12") (pin "1") (pinfunction "1_1") (pintype "passive"))
    )
    (net (code "60") (name "Net-(Q1-G)") (class "Default")
      (node (ref "Q1") (pin "1") (pinfunction "G_1") (pintype "passive"))
      (node (ref "R6") (pin "2") (pintype "passive"))
      (node (ref "R7") (pin "1") (pintype "passive"))
    )
    (net (code "61") (name "Net-(Q2-B)") (class "Default")
      (node (ref "Q2") (pin "1") (pinfunction "B_1") (pintype "passive"))
      (node (ref "R10") (pin "1") (pinfunction "1_1") (pintype "passive"))
      (node (ref "R13") (pin "2") (pinfunction "2_2") (pintype "passive"))
    )
    (net (code "62") (name "Net-(Q2-C)") (class "Default")
      (node (ref "Q2") (pin "3") (pinfunction "C_3") (pintype "passive"))
      (node (ref "R7") (pin "2") (pintype "passive"))
    )
    (net (code "63") (name "Net-(Q3-D)") (class "Default")
      (node (ref "C15") (pin "1") (pinfunction "1_1") (pintype "passive"))
      (node (ref "CN1") (pin "2") (pinfunction "2_2") (pintype "passive"))
      (node (ref "Q3") (pin "3") (pinfunction "D_3") (pintype "passive"))
    )
    (net (code "64") (name "Net-(Q3-G)") (class "Default")
      (node (ref "Q3") (pin "1") (pinfunction "G_1") (pintype "passive"))
      (node (ref "R19") (pin "1") (pinfunction "1_1") (pintype "passive"))
      (node (ref "R20") (pin "2") (pinfunction "2_2") (pintype "passive"))
    )
    (net (code "65") (name "Net-(Q4-G)") (class "Default")
      (node (ref "Q4") (pin "1") (pinfunction "G_1") (pintype "passive"))
      (node (ref "R29") (pin "2") (pintype "passive"))
      (node (ref "R32") (pin "1") (pintype "passive"))
    )
    (net (code "66") (name "Net-(Q5-B)") (class "Default")
      (node (ref "Q5") (pin "1") (pinfunction "B_1") (pintype "passive"))
      (node (ref "R33") (pin "1") (pinfunction "1_1") (pintype "passive"))
      (node (ref "R34") (pin "2") (pinfunction "2_2") (pintype "passive"))
    )
    (net (code "67") (name "Net-(Q5-C)") (class "Default")
      (node (ref "Q5") (pin "3") (pinfunction "C_3") (pintype "passive"))
      (node (ref "R32") (pin "2") (pintype "passive"))
    )
    (net (code "68") (name "Net-(Q7-DRAIN)") (class "Default")
      (node (ref "Q7") (pin "3") (pinfunction "DRAIN_3") (pintype "passive"))
      (node (ref "R40") (pin "1") (pinfunction "1_1") (pintype "passive"))
    )
    (net (code "69") (name "Net-(R12-Pad2)") (class "Default")
      (node (ref "R12") (pin "2") (pinfunction "2_2") (pintype "passive"))
      (node (ref "R16") (pin "2") (pinfunction "2_2") (pintype "passive"))
      (node (ref "R17") (pin "1") (pinfunction "1_1") (pintype "passive"))
    )
    (net (code "70") (name "Net-(U1-PROG)") (class "Default")
      (node (ref "R1") (pin "2") (pinfunction "2_2") (pintype "passive"))
      (node (ref "R40") (pin "2") (pinfunction "2_2") (pintype "passive"))
      (node (ref "U1") (pin "2") (pinfunction "PROG_2") (pintype "passive"))
    )
    (net (code "71") (name "Net-(U1-VCC)") (class "Default")
      (node (ref "C6") (pin "2") (pintype "passive"))
      (node (ref "R3") (pin "1") (pinfunction "1_1") (pintype "passive"))
      (node (ref "U1") (pin "4") (pinfunction "VCC_4") (pintype "passive"))
    )
    (net (code "72") (name "Net-(U2-EN)") (class "Default")
      (node (ref "R2") (pin "2") (pinfunction "2_2") (pintype "passive"))
      (node (ref "U2") (pin "3") (pinfunction "EN_3") (pintype "passive"))
    )
    (net (code "73") (name "Net-(U3-VDD1V2)") (class "Default")
      (node (ref "C22") (pin "2") (pintype "passive"))
      (node (ref "U3") (pin "17") (pinfunction "VDD1V2_17") (pintype "passive"))
    )
    (net (code "74") (name "Net-(U4-1B)") (class "Default")
      (node (ref "R21") (pin "1") (pinfunction "1_1") (pintype "passive"))
      (node (ref "U4") (pin "1") (pinfunction "1B_1") (pintype "passive"))
    )
    (net (code "75") (name "Net-(U4-2B)") (class "Default")
      (node (ref "R22") (pin "1") (pinfunction "1_1") (pintype "passive"))
      (node (ref "U4") (pin "2") (pinfunction "2B_2") (pintype "passive"))
    )
    (net (code "76") (name "Net-(U4-3B)") (class "Default")
      (node (ref "R23") (pin "1") (pinfunction "1_1") (pintype "passive"))
      (node (ref "U4") (pin "3") (pinfunction "3B_3") (pintype "passive"))
    )
    (net (code "77") (name "Net-(U4-4B)") (class "Default")
      (node (ref "R24") (pin "1") (pinfunction "1_1") (pintype "passive"))
      (node (ref "U4") (pin "4") (pinfunction "4B_4") (pintype "passive"))
    )
    (net (code "78") (name "Net-(U5-LX)") (class "Default")
      (node (ref "L4") (pin "2") (pinfunction "2_2") (pintype "passive"))
      (node (ref "U5") (pin "2") (pinfunction "LX_2") (pintype "passive"))
    )
    (net (code "79") (name "Net-(U6-1B)") (class "Default")
      (node (ref "R25") (pin "1") (pinfunction "1_1") (pintype "passive"))
      (node (ref "U6") (pin "1") (pinfunction "1B_1") (pintype "passive"))
    )
    (net (code "80") (name "Net-(U6-2B)") (class "Default")
      (node (ref "R26") (pin "1") (pinfunction "1_1") (pintype "passive"))
      (node (ref "U6") (pin "2") (pinfunction "2B_2") (pintype "passive"))
    )
    (net (code "81") (name "Net-(U6-3B)") (class "Default")
      (node (ref "R27") (pin "1") (pinfunction "1_1") (pintype "passive"))
      (node (ref "U6") (pin "3") (pinfunction "3B_3") (pintype "passive"))
    )
    (net (code "82") (name "Net-(U6-4B)") (class "Default")
      (node (ref "R28") (pin "1") (pinfunction "1_1") (pintype "passive"))
      (node (ref "U6") (pin "4") (pinfunction "4B_4") (pintype "passive"))
    )
    (net (code "83") (name "VBUS_BAT") (class "Default")
      (node (ref "C2") (pin "2") (pinfunction "2_2") (pintype "passive"))
      (node (ref "C20") (pin "1") (pinfunction "1_1") (pintype "passive"))
      (node (ref "C21") (pin "2") (pinfunction "2_2") (pintype "passive"))
      (node (ref "D7") (pin "2") (pinfunction "K_2") (pintype "passive"))
      (node (ref "J1") (pin "5") (pinfunction "5_5") (pintype "passive"))
      (node (ref "J2") (pin "5") (pinfunction "5_5") (pintype "passive"))
      (node (ref "Q4") (pin "2") (pinfunction "S_2") (pintype "passive"))
      (node (ref "Q6") (pin "2") (pinfunction "S_2") (pintype "passive"))
      (node (ref "R2") (pin "1") (pinfunction "1_1") (pintype "passive"))
      (node (ref "R29") (pin "1") (pintype "passive"))
      (node (ref "U2") (pin "1") (pinfunction "VIN_1") (pintype "passive"))
      (node (ref "U4") (pin "6") (pinfunction "COM_6") (pintype "passive"))
      (node (ref "U6") (pin "6") (pinfunction "COM_6") (pintype "passive"))
    )
    (net (code "84") (name "VCC_USB") (class "Default")
      (node (ref "C1") (pin "2") (pinfunction "2_2") (pintype "passive"))
      (node (ref "D1") (pin "2") (pinfunction "2_2") (pintype "passive"))
      (node (ref "D7") (pin "1") (pinfunction "A_1") (pintype "passive"))
      (node (ref "Q6") (pin "1") (pinfunction "G_1") (pintype "passive"))
      (node (ref "R3") (pin "2") (pinfunction "2_2") (pintype "passive"))
      (node (ref "R35") (pin "1") (pinfunction "1_1") (pintype "passive"))
      (node (ref "R37") (pin "2") (pinfunction "2_2") (pintype "passive"))
      (node (ref "USB1") (pin "A9") (pinfunction "VBUS_A9") (pintype "passive"))
      (node (ref "USB1") (pin "B9") (pinfunction "VBUS_B9") (pintype "passive"))
    )
    (net (code "85") (name "unconnected-(BAT1-Pad4)") (class "Default")
      (node (ref "BAT1") (pin "4") (pinfunction "4_4") (pintype "passive"))
    )
    (net (code "86") (name "unconnected-(BAT1-Pad5)") (class "Default")
      (node (ref "BAT1") (pin "5") (pinfunction "5_5") (pintype "passive"))
    )
    (net (code "87") (name "unconnected-(CN1-Pad3)") (class "Default")
      (node (ref "CN1") (pin "3") (pinfunction "3_3") (pintype "passive"))
    )
    (net (code "88") (name "unconnected-(CN1-Pad4)") (class "Default")
      (node (ref "CN1") (pin "4") (pinfunction "4_4") (pintype "passive"))
    )
    (net (code "89") (name "unconnected-(CN2-Pad5)") (class "Default")
      (node (ref "CN2") (pin "5") (pinfunction "5_5") (pintype "passive"))
    )
    (net (code "90") (name "unconnected-(CN2-Pad6)") (class "Default")
      (node (ref "CN2") (pin "6") (pinfunction "6_6") (pintype "passive"))
    )
    (net (code "91") (name "unconnected-(J1-Pad6)") (class "Default")
      (node (ref "J1") (pin "6") (pinfunction "6_6") (pintype "passive"))
    )
    (net (code "92") (name "unconnected-(J1-Pad7)") (class "Default")
      (node (ref "J1") (pin "7") (pinfunction "7_7") (pintype "passive"))
    )
    (net (code "93") (name "unconnected-(J2-Pad6)") (class "Default")
      (node (ref "J2") (pin "6") (pinfunction "6_6") (pintype "passive"))
    )
    (net (code "94") (name "unconnected-(J2-Pad7)") (class "Default")
      (node (ref "J2") (pin "7") (pinfunction "7_7") (pintype "passive"))
    )
    (net (code "95") (name "unconnected-(P1-Pad1)") (class "Default")
      (node (ref "P1") (pin "1") (pinfunction "1_1") (pintype "passive"))
    )
    (net (code "96") (name "unconnected-(U1-STDBY-Pad6)") (class "Default")
      (node (ref "U1") (pin "6") (pinfunction "STDBY_6") (pintype "passive"))
    )
    (net (code "97") (name "unconnected-(U2-NC-Pad4)") (class "Default")
      (node (ref "U2") (pin "4") (pinfunction "NC_4") (pintype "passive"))
    )
    (net (code "98") (name "unconnected-(U3-PC[7]-Pad33)") (class "Default")
      (node (ref "U3") (pin "33") (pinfunction "PC[7]_33") (pintype "passive"))
    )
    (net (code "99") (name "unconnected-(U3-PD[0]-Pad36)") (class "Default")
      (node (ref "U3") (pin "36") (pinfunction "PD[0]_36") (pintype "passive"))
    )
    (net (code "100") (name "unconnected-(U3-PD[1]-Pad37)") (class "Default")
      (node (ref "U3") (pin "37") (pinfunction "PD[1]_37") (pintype "passive"))
    )
    (net (code "101") (name "unconnected-(U3-PF[1]-Pad35)") (class "Default")
      (node (ref "U3") (pin "35") (pinfunction "PF[1]_35") (pintype "passive"))
    )
  )
)
